# onboard_3.net
KiCad netlist of a schematic drawn in EAGLE
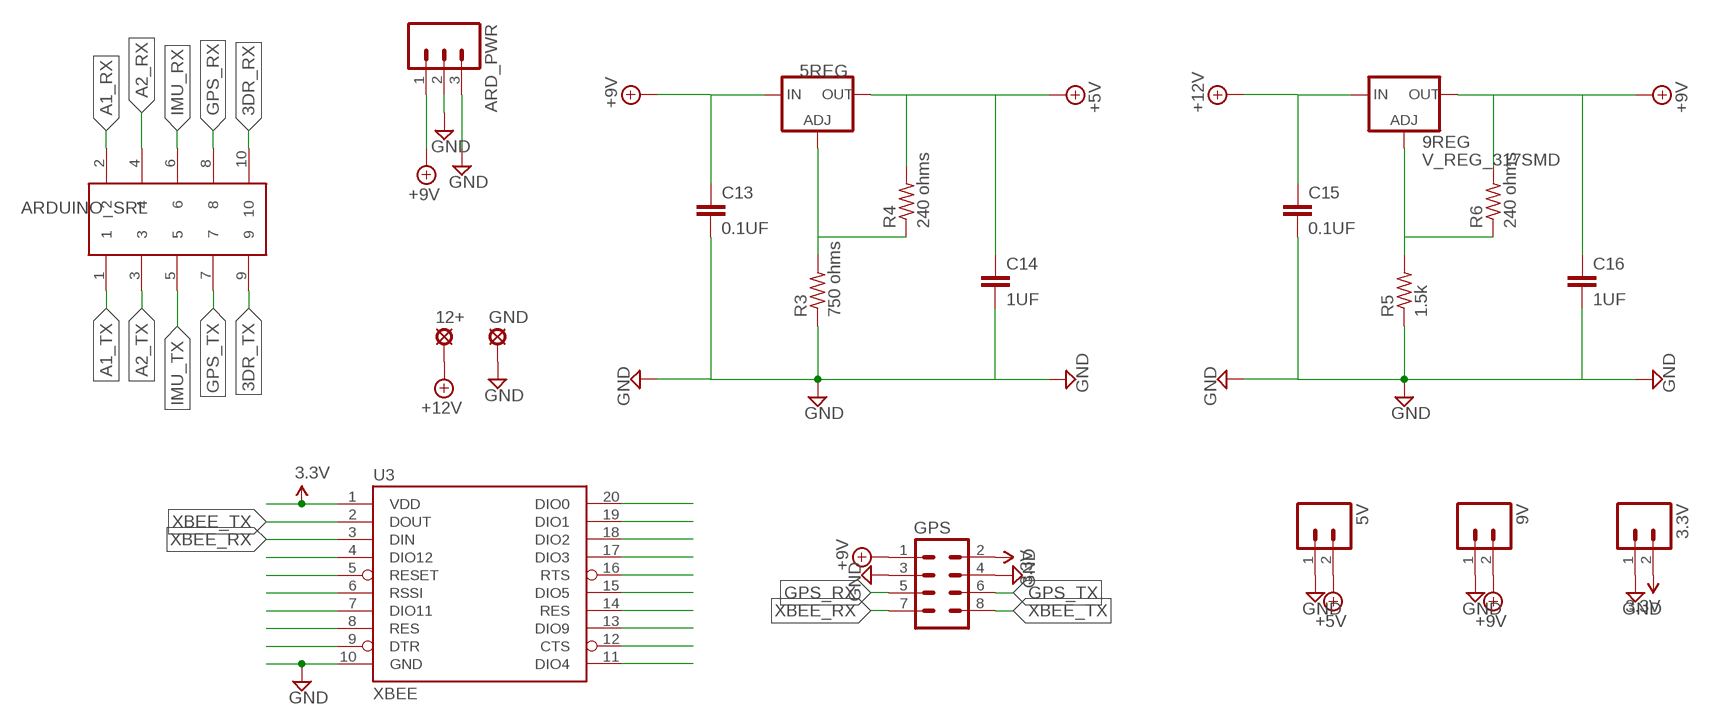
[diagram p0: schematic, sheet 1, part 1 of 2]
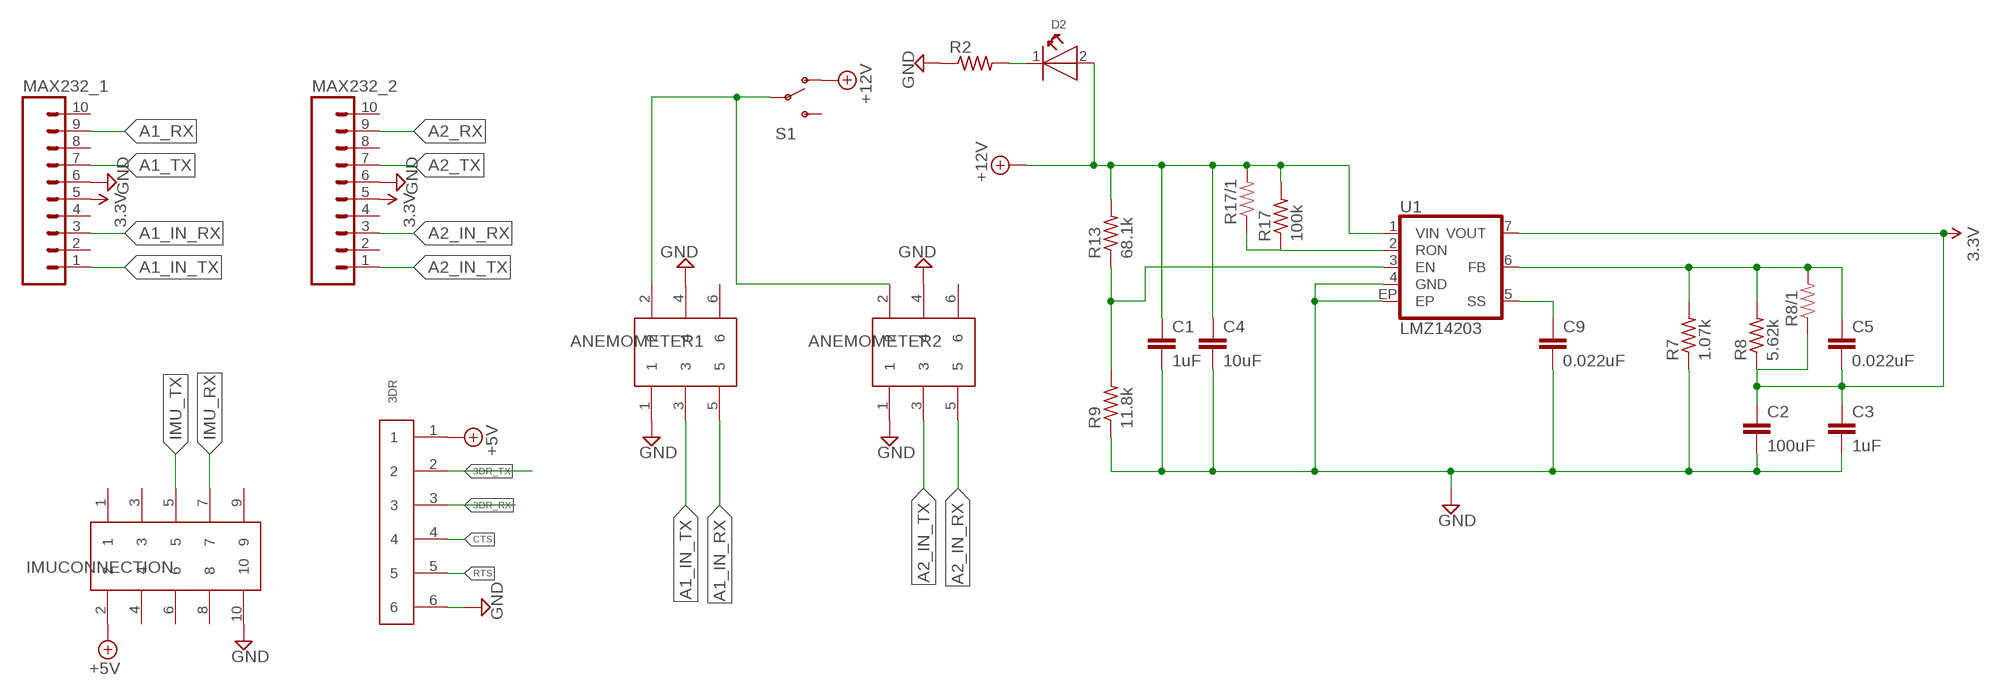
[diagram p1: schematic, sheet 1, part 2 of 2]

(export (version "E")
  (design (tool "Eeschema 10.0.6"))
  (components
    (comp (ref "3.3V")
      (value "M02")
      (footprint "eagle-import:02P")
      (libsource (lib "eagle-import") (part "M02"))
    )
    (comp (ref "3DR")
      (value "653006114822")
      (footprint "eagle-import:653006114822")
      (libsource (lib "eagle-import") (part "653006114822"))
    )
    (comp (ref "5REG")
      (value "V_REG_317SMD")
      (footprint "eagle-import:SOT223")
      (libsource (lib "eagle-import") (part "V_REG_317SMD"))
    )
    (comp (ref "5V")
      (value "M02")
      (footprint "eagle-import:02P")
      (libsource (lib "eagle-import") (part "M02"))
    )
    (comp (ref "9REG")
      (value "V_REG_317SMD")
      (footprint "eagle-import:SOT223")
      (libsource (lib "eagle-import") (part "V_REG_317SMD"))
    )
    (comp (ref "9V")
      (value "M02")
      (footprint "eagle-import:02P")
      (libsource (lib "eagle-import") (part "M02"))
    )
    (comp (ref "12+")
      (value "SE14")
      (footprint "eagle-import:SE14")
      (libsource (lib "eagle-import") (part "SE14"))
    )
    (comp (ref "ANEMOMETER1")
      (value "61200622323")
      (footprint "eagle-import:61200622323")
      (libsource (lib "eagle-import") (part "61200622323"))
    )
    (comp (ref "ANEMOMETER2")
      (value "61200622323")
      (footprint "eagle-import:61200622323")
      (libsource (lib "eagle-import") (part "61200622323"))
    )
    (comp (ref "ARDUINO_SRL")
      (value "61201022323")
      (footprint "eagle-import:61201022323")
      (libsource (lib "eagle-import") (part "61201022323"))
    )
    (comp (ref "ARD_PWR")
      (value "M03")
      (footprint "eagle-import:03P")
      (libsource (lib "eagle-import") (part "M03"))
    )
    (comp (ref "C1")
      (value "1uF")
      (footprint "eagle-import:0805")
      (fields (field (name "MF") "VISHAY/SPRAGUE") (field (name "MPN") "1C10Z5U104M050R"))
      (libsource (lib "eagle-import") (part "1UF-25V-10%(0805)"))
    )
    (comp (ref "C2")
      (value "100uF")
      (footprint "eagle-import:1206")
      (libsource (lib "eagle-import") (part "CAP1206"))
    )
    (comp (ref "C3")
      (value "1uF")
      (footprint "eagle-import:0805")
      (fields (field (name "MF") "VISHAY/SPRAGUE") (field (name "MPN") "1C10Z5U104M050R"))
      (libsource (lib "eagle-import") (part "1UF-25V-10%(0805)"))
    )
    (comp (ref "C4")
      (value "10uF")
      (footprint "eagle-import:0805")
      (libsource (lib "eagle-import") (part "CAP0805"))
    )
    (comp (ref "C5")
      (value "0.022uF")
      (footprint "eagle-import:0603-CAP")
      (libsource (lib "eagle-import") (part "CAP0603-CAP"))
    )
    (comp (ref "C9")
      (value "0.022uF")
      (footprint "eagle-import:0603-CAP")
      (libsource (lib "eagle-import") (part "CAP0603-CAP"))
    )
    (comp (ref "C13")
      (value "0.1UF")
      (footprint "eagle-import:0805")
      (libsource (lib "eagle-import") (part "1UF-25V-10%(0805)"))
    )
    (comp (ref "C14")
      (value "1UF")
      (footprint "eagle-import:0805")
      (libsource (lib "eagle-import") (part "1UF-25V-10%(0805)"))
    )
    (comp (ref "C15")
      (value "0.1UF")
      (footprint "eagle-import:0805")
      (libsource (lib "eagle-import") (part "1UF-25V-10%(0805)"))
    )
    (comp (ref "C16")
      (value "1UF")
      (footprint "eagle-import:0805")
      (libsource (lib "eagle-import") (part "1UF-25V-10%(0805)"))
    )
    (comp (ref "D2")
      (value "WL-SMCW-150120BS75000-B")
      (footprint "eagle-import:1206")
      (fields
        (field (name "MANUFACTURER") "Würth Elektronik eiSos GmbH")
        (field (name "CREATED-BY") "Christin Otto")
      )
      (libsource (lib "eagle-import") (part "WL-SMCW-150120BS75000-B"))
    )
    (comp (ref "GND")
      (value "SE14")
      (footprint "eagle-import:SE14")
      (libsource (lib "eagle-import") (part "SE14"))
    )
    (comp (ref "GPS")
      (value "M04X2")
      (footprint "eagle-import:2X4")
      (libsource (lib "eagle-import") (part "M04X2"))
    )
    (comp (ref "IMUCONNECTION")
      (value "62501021621")
      (footprint "eagle-import:62501021621")
      (libsource (lib "eagle-import") (part "62501021621"))
    )
    (comp (ref "MAX232_1")
      (value "M10")
      (footprint "eagle-import:10P")
      (libsource (lib "eagle-import") (part "M10"))
    )
    (comp (ref "MAX232_2")
      (value "M10")
      (footprint "eagle-import:10P")
      (libsource (lib "eagle-import") (part "M10"))
    )
    (comp (ref "R2")
      (value "R-US_M2012")
      (footprint "eagle-import:M2012")
      (libsource (lib "eagle-import") (part "resistor_R-US_M2012"))
    )
    (comp (ref "R3")
      (value "750 ohms")
      (footprint "eagle-import:M2012")
      (libsource (lib "eagle-import") (part "R-US_M2012"))
    )
    (comp (ref "R4")
      (value "240 ohms")
      (footprint "eagle-import:M2012")
      (libsource (lib "eagle-import") (part "R-US_M2012"))
    )
    (comp (ref "R5")
      (value "1.5k")
      (footprint "eagle-import:M2012")
      (libsource (lib "eagle-import") (part "R-US_M2012"))
    )
    (comp (ref "R6")
      (value "240 ohms")
      (footprint "eagle-import:M2012")
      (libsource (lib "eagle-import") (part "R-US_M2012"))
    )
    (comp (ref "R7")
      (value "1.07k")
      (footprint "eagle-import:M2012")
      (libsource (lib "eagle-import") (part "resistor_R-US_M2012"))
    )
    (comp (ref "R8")
      (value "5.62k")
      (footprint "eagle-import:M2012")
      (libsource (lib "eagle-import") (part "resistor_R-US_M2012"))
    )
    (comp (ref "R8/1")
      (value "RESISTORPTH-1/2W")
      (footprint "eagle-import:AXIAL-0.5")
      (libsource (lib "eagle-import") (part "RESISTORPTH-1/2W"))
    )
    (comp (ref "R9")
      (value "11.8k")
      (footprint "eagle-import:M2012")
      (libsource (lib "eagle-import") (part "resistor_R-US_M2012"))
    )
    (comp (ref "R13")
      (value "68.1k")
      (footprint "eagle-import:M2012")
      (libsource (lib "eagle-import") (part "resistor_R-US_M2012"))
    )
    (comp (ref "R17")
      (value "100k")
      (footprint "eagle-import:M2012")
      (libsource (lib "eagle-import") (part "resistor_R-US_M2012"))
    )
    (comp (ref "R17/1")
      (value "RESISTORPTH-1/2W")
      (footprint "eagle-import:AXIAL-0.5")
      (libsource (lib "eagle-import") (part "RESISTORPTH-1/2W"))
    )
    (comp (ref "S1")
      (value "SWITCH-SPDTSMD2")
      (footprint "eagle-import:SWITCH-SPDT-SMD")
      (libsource (lib "eagle-import") (part "SWITCH-SPDTSMD2"))
    )
    (comp (ref "U1")
      (value "LMZ14203")
      (footprint "eagle-import:TO-PMOD-7")
      (libsource (lib "eagle-import") (part "LMZ14203"))
    )
    (comp (ref "U3")
      (value "XBEE")
      (footprint "eagle-import:XBEE-1")
      (libsource (lib "eagle-import") (part "XBEE-1B1"))
    )
  )
  (nets
    (net (code "1") (name "+5V") (class "Default")
      (node (ref "3DR") (pin "1") (pinfunction "1_1") (pintype "passive"))
      (node (ref "5REG") (pin "2") (pinfunction "OUT_2") (pintype "output"))
      (node (ref "5V") (pin "2") (pinfunction "2_2") (pintype "passive"))
      (node (ref "C14") (pin "1") (pinfunction "1_1") (pintype "passive"))
      (node (ref "IMUCONNECTION") (pin "2") (pinfunction "2_2") (pintype "passive"))
      (node (ref "R4") (pin "2") (pinfunction "2_2") (pintype "passive"))
    )
    (net (code "2") (name "+9V") (class "Default")
      (node (ref "5REG") (pin "3") (pinfunction "IN_3") (pintype "input"))
      (node (ref "9REG") (pin "2") (pinfunction "OUT_2") (pintype "output"))
      (node (ref "9V") (pin "2") (pinfunction "2_2") (pintype "passive"))
      (node (ref "ARD_PWR") (pin "1") (pinfunction "1_1") (pintype "passive"))
      (node (ref "C13") (pin "1") (pinfunction "1_1") (pintype "passive"))
      (node (ref "C16") (pin "1") (pinfunction "1_1") (pintype "passive"))
      (node (ref "GPS") (pin "1") (pinfunction "1_1") (pintype "passive"))
      (node (ref "R6") (pin "2") (pinfunction "2_2") (pintype "passive"))
    )
    (net (code "3") (name "+12V") (class "Default")
      (node (ref "12+") (pin "MP") (pinfunction "MP_MP") (pintype "passive"))
      (node (ref "9REG") (pin "3") (pinfunction "IN_3") (pintype "input"))
      (node (ref "C1") (pin "1") (pinfunction "1_1") (pintype "passive"))
      (node (ref "C15") (pin "1") (pinfunction "1_1") (pintype "passive"))
      (node (ref "C4") (pin "1") (pinfunction "1_1") (pintype "passive"))
      (node (ref "D2") (pin "2") (pinfunction "A_2") (pintype "bidirectional"))
      (node (ref "R13") (pin "2") (pinfunction "2_2") (pintype "passive"))
      (node (ref "R17") (pin "2") (pinfunction "2_2") (pintype "passive"))
      (node (ref "R17/1") (pin "P$2") (pinfunction "2_P$2") (pintype "passive"))
      (node (ref "S1") (pin "1") (pinfunction "O_1") (pintype "passive"))
      (node (ref "U1") (pin "1") (pinfunction "VIN_1") (pintype "bidirectional"))
    )
    (net (code "4") (name "3.3V") (class "Default")
      (node (ref "3.3V") (pin "2") (pinfunction "2_2") (pintype "passive"))
      (node (ref "C2") (pin "1") (pinfunction "1_1") (pintype "passive"))
      (node (ref "C3") (pin "1") (pinfunction "1_1") (pintype "passive"))
      (node (ref "C5") (pin "2") (pinfunction "2_2") (pintype "passive"))
      (node (ref "GPS") (pin "2") (pinfunction "2_2") (pintype "passive"))
      (node (ref "MAX232_1") (pin "5") (pinfunction "5_5") (pintype "passive"))
      (node (ref "MAX232_2") (pin "5") (pinfunction "5_5") (pintype "passive"))
      (node (ref "R8") (pin "1") (pinfunction "1_1") (pintype "passive"))
      (node (ref "R8/1") (pin "P$1") (pinfunction "1_P$1") (pintype "passive"))
      (node (ref "U1") (pin "7") (pinfunction "VOUT_7") (pintype "bidirectional"))
      (node (ref "U3") (pin "1") (pinfunction "VDD_1") (pintype "power_in"))
    )
    (net (code "5") (name "3DR_RX") (class "Default")
      (node (ref "3DR") (pin "3") (pinfunction "3_3") (pintype "passive"))
      (node (ref "ARDUINO_SRL") (pin "10") (pinfunction "10_10") (pintype "passive"))
    )
    (net (code "6") (name "3DR_TX") (class "Default")
      (node (ref "3DR") (pin "2") (pinfunction "2_2") (pintype "passive"))
      (node (ref "ARDUINO_SRL") (pin "9") (pinfunction "9_9") (pintype "passive"))
    )
    (net (code "7") (name "A1_IN_RX") (class "Default")
      (node (ref "ANEMOMETER1") (pin "5") (pinfunction "5_5") (pintype "passive"))
      (node (ref "MAX232_1") (pin "3") (pinfunction "3_3") (pintype "passive"))
    )
    (net (code "8") (name "A1_IN_TX") (class "Default")
      (node (ref "ANEMOMETER1") (pin "3") (pinfunction "3_3") (pintype "passive"))
      (node (ref "MAX232_1") (pin "1") (pinfunction "1_1") (pintype "passive"))
    )
    (net (code "9") (name "A1_RX") (class "Default")
      (node (ref "ARDUINO_SRL") (pin "2") (pinfunction "2_2") (pintype "passive"))
      (node (ref "MAX232_1") (pin "9") (pinfunction "9_9") (pintype "passive"))
    )
    (net (code "10") (name "A1_TX") (class "Default")
      (node (ref "ARDUINO_SRL") (pin "1") (pinfunction "1_1") (pintype "passive"))
      (node (ref "MAX232_1") (pin "7") (pinfunction "7_7") (pintype "passive"))
    )
    (net (code "11") (name "A2_IN_RX") (class "Default")
      (node (ref "ANEMOMETER2") (pin "5") (pinfunction "5_5") (pintype "passive"))
      (node (ref "MAX232_2") (pin "3") (pinfunction "3_3") (pintype "passive"))
    )
    (net (code "12") (name "A2_IN_TX") (class "Default")
      (node (ref "ANEMOMETER2") (pin "3") (pinfunction "3_3") (pintype "passive"))
      (node (ref "MAX232_2") (pin "1") (pinfunction "1_1") (pintype "passive"))
    )
    (net (code "13") (name "A2_RX") (class "Default")
      (node (ref "ARDUINO_SRL") (pin "4") (pinfunction "4_4") (pintype "passive"))
      (node (ref "MAX232_2") (pin "9") (pinfunction "9_9") (pintype "passive"))
    )
    (net (code "14") (name "A2_TX") (class "Default")
      (node (ref "ARDUINO_SRL") (pin "3") (pinfunction "3_3") (pintype "passive"))
      (node (ref "MAX232_2") (pin "7") (pinfunction "7_7") (pintype "passive"))
    )
    (net (code "15") (name "CTS") (class "Default")
      (node (ref "3DR") (pin "4") (pinfunction "4_4") (pintype "passive"))
    )
    (net (code "16") (name "GND") (class "Default")
      (node (ref "3.3V") (pin "1") (pinfunction "1_1") (pintype "passive"))
      (node (ref "3DR") (pin "6") (pinfunction "6_6") (pintype "passive"))
      (node (ref "5V") (pin "1") (pinfunction "1_1") (pintype "passive"))
      (node (ref "9V") (pin "1") (pinfunction "1_1") (pintype "passive"))
      (node (ref "ANEMOMETER1") (pin "1") (pinfunction "1_1") (pintype "passive"))
      (node (ref "ANEMOMETER1") (pin "4") (pinfunction "4_4") (pintype "passive"))
      (node (ref "ANEMOMETER2") (pin "1") (pinfunction "1_1") (pintype "passive"))
      (node (ref "ANEMOMETER2") (pin "4") (pinfunction "4_4") (pintype "passive"))
      (node (ref "ARD_PWR") (pin "2") (pinfunction "2_2") (pintype "passive"))
      (node (ref "ARD_PWR") (pin "3") (pinfunction "3_3") (pintype "passive"))
      (node (ref "C1") (pin "2") (pinfunction "2_2") (pintype "passive"))
      (node (ref "C13") (pin "2") (pinfunction "2_2") (pintype "passive"))
      (node (ref "C14") (pin "2") (pinfunction "2_2") (pintype "passive"))
      (node (ref "C15") (pin "2") (pinfunction "2_2") (pintype "passive"))
      (node (ref "C16") (pin "2") (pinfunction "2_2") (pintype "passive"))
      (node (ref "C2") (pin "2") (pinfunction "2_2") (pintype "passive"))
      (node (ref "C3") (pin "2") (pinfunction "2_2") (pintype "passive"))
      (node (ref "C4") (pin "2") (pinfunction "2_2") (pintype "passive"))
      (node (ref "C9") (pin "2") (pinfunction "2_2") (pintype "passive"))
      (node (ref "GND") (pin "MP") (pinfunction "MP_MP") (pintype "passive"))
      (node (ref "GPS") (pin "3") (pinfunction "3_3") (pintype "passive"))
      (node (ref "GPS") (pin "4") (pinfunction "4_4") (pintype "passive"))
      (node (ref "IMUCONNECTION") (pin "10") (pinfunction "10_10") (pintype "passive"))
      (node (ref "MAX232_1") (pin "6") (pinfunction "6_6") (pintype "passive"))
      (node (ref "MAX232_2") (pin "6") (pinfunction "6_6") (pintype "passive"))
      (node (ref "R2") (pin "1") (pinfunction "1_1") (pintype "passive"))
      (node (ref "R3") (pin "1") (pinfunction "1_1") (pintype "passive"))
      (node (ref "R5") (pin "1") (pinfunction "1_1") (pintype "passive"))
      (node (ref "R7") (pin "1") (pinfunction "1_1") (pintype "passive"))
      (node (ref "R9") (pin "1") (pinfunction "1_1") (pintype "passive"))
      (node (ref "U1") (pin "4") (pinfunction "GND_4") (pintype "bidirectional"))
      (node (ref "U1") (pin "EP") (pinfunction "EP_EP") (pintype "bidirectional"))
      (node (ref "U3") (pin "10") (pinfunction "GND_10") (pintype "power_in"))
    )
    (net (code "17") (name "GPS_RX") (class "Default")
      (node (ref "ARDUINO_SRL") (pin "8") (pinfunction "8_8") (pintype "passive"))
      (node (ref "GPS") (pin "5") (pinfunction "5_5") (pintype "passive"))
    )
    (net (code "18") (name "GPS_TX") (class "Default")
      (node (ref "ARDUINO_SRL") (pin "7") (pinfunction "7_7") (pintype "passive"))
      (node (ref "GPS") (pin "6") (pinfunction "6_6") (pintype "passive"))
    )
    (net (code "19") (name "IMU_RX") (class "Default")
      (node (ref "ARDUINO_SRL") (pin "6") (pinfunction "6_6") (pintype "passive"))
      (node (ref "IMUCONNECTION") (pin "7") (pinfunction "7_7") (pintype "passive"))
    )
    (net (code "20") (name "IMU_TX") (class "Default")
      (node (ref "ARDUINO_SRL") (pin "5") (pinfunction "5_5") (pintype "passive"))
      (node (ref "IMUCONNECTION") (pin "5") (pinfunction "5_5") (pintype "passive"))
    )
    (net (code "21") (name "Net-(5REG-ADJ)") (class "Default")
      (node (ref "5REG") (pin "1") (pinfunction "ADJ_1") (pintype "input"))
      (node (ref "R3") (pin "2") (pinfunction "2_2") (pintype "passive"))
      (node (ref "R4") (pin "1") (pinfunction "1_1") (pintype "passive"))
    )
    (net (code "22") (name "Net-(9REG-ADJ)") (class "Default")
      (node (ref "9REG") (pin "1") (pinfunction "ADJ_1") (pintype "input"))
      (node (ref "R5") (pin "2") (pinfunction "2_2") (pintype "passive"))
      (node (ref "R6") (pin "1") (pinfunction "1_1") (pintype "passive"))
    )
    (net (code "23") (name "Net-(D2-K)") (class "Default")
      (node (ref "D2") (pin "1") (pinfunction "K_1") (pintype "bidirectional"))
      (node (ref "R2") (pin "2") (pinfunction "2_2") (pintype "passive"))
    )
    (net (code "24") (name "Net-(R8/1-2)") (class "Default")
      (node (ref "C5") (pin "1") (pinfunction "1_1") (pintype "passive"))
      (node (ref "R7") (pin "2") (pinfunction "2_2") (pintype "passive"))
      (node (ref "R8") (pin "2") (pinfunction "2_2") (pintype "passive"))
      (node (ref "R8/1") (pin "P$2") (pinfunction "2_P$2") (pintype "passive"))
      (node (ref "U1") (pin "6") (pinfunction "FB_6") (pintype "bidirectional"))
    )
    (net (code "25") (name "Net-(R17/1-1)") (class "Default")
      (node (ref "R17") (pin "1") (pinfunction "1_1") (pintype "passive"))
      (node (ref "R17/1") (pin "P$1") (pinfunction "1_P$1") (pintype "passive"))
      (node (ref "U1") (pin "2") (pinfunction "RON_2") (pintype "bidirectional"))
    )
    (net (code "26") (name "Net-(S1-P)") (class "Default")
      (node (ref "ANEMOMETER1") (pin "2") (pinfunction "2_2") (pintype "passive"))
      (node (ref "ANEMOMETER2") (pin "2") (pinfunction "2_2") (pintype "passive"))
      (node (ref "S1") (pin "2") (pinfunction "P_2") (pintype "passive"))
    )
    (net (code "27") (name "Net-(U1-EN)") (class "Default")
      (node (ref "R13") (pin "1") (pinfunction "1_1") (pintype "passive"))
      (node (ref "R9") (pin "2") (pinfunction "2_2") (pintype "passive"))
      (node (ref "U1") (pin "3") (pinfunction "EN_3") (pintype "bidirectional"))
    )
    (net (code "28") (name "Net-(U1-SS)") (class "Default")
      (node (ref "C9") (pin "1") (pinfunction "1_1") (pintype "passive"))
      (node (ref "U1") (pin "5") (pinfunction "SS_5") (pintype "bidirectional"))
    )
    (net (code "29") (name "RTS") (class "Default")
      (node (ref "3DR") (pin "5") (pinfunction "5_5") (pintype "passive"))
    )
    (net (code "30") (name "XBEE_RX") (class "Default")
      (node (ref "GPS") (pin "7") (pinfunction "7_7") (pintype "passive"))
      (node (ref "U3") (pin "3") (pinfunction "DIN_3") (pintype "input"))
    )
    (net (code "31") (name "XBEE_TX") (class "Default")
      (node (ref "GPS") (pin "8") (pinfunction "8_8") (pintype "passive"))
      (node (ref "U3") (pin "2") (pinfunction "DOUT_2") (pintype "output"))
    )
    (net (code "32") (name "unconnected-(ANEMOMETER1-Pad6)") (class "Default")
      (node (ref "ANEMOMETER1") (pin "6") (pinfunction "6_6") (pintype "passive"))
    )
    (net (code "33") (name "unconnected-(ANEMOMETER2-Pad6)") (class "Default")
      (node (ref "ANEMOMETER2") (pin "6") (pinfunction "6_6") (pintype "passive"))
    )
    (net (code "34") (name "unconnected-(IMUCONNECTION-Pad1)") (class "Default")
      (node (ref "IMUCONNECTION") (pin "1") (pinfunction "1_1") (pintype "passive"))
    )
    (net (code "35") (name "unconnected-(IMUCONNECTION-Pad3)") (class "Default")
      (node (ref "IMUCONNECTION") (pin "3") (pinfunction "3_3") (pintype "passive"))
    )
    (net (code "36") (name "unconnected-(IMUCONNECTION-Pad4)") (class "Default")
      (node (ref "IMUCONNECTION") (pin "4") (pinfunction "4_4") (pintype "passive"))
    )
    (net (code "37") (name "unconnected-(IMUCONNECTION-Pad6)") (class "Default")
      (node (ref "IMUCONNECTION") (pin "6") (pinfunction "6_6") (pintype "passive"))
    )
    (net (code "38") (name "unconnected-(IMUCONNECTION-Pad8)") (class "Default")
      (node (ref "IMUCONNECTION") (pin "8") (pinfunction "8_8") (pintype "passive"))
    )
    (net (code "39") (name "unconnected-(IMUCONNECTION-Pad9)") (class "Default")
      (node (ref "IMUCONNECTION") (pin "9") (pinfunction "9_9") (pintype "passive"))
    )
    (net (code "40") (name "unconnected-(MAX232_1-Pad2)") (class "Default")
      (node (ref "MAX232_1") (pin "2") (pinfunction "2_2") (pintype "passive"))
    )
    (net (code "41") (name "unconnected-(MAX232_1-Pad4)") (class "Default")
      (node (ref "MAX232_1") (pin "4") (pinfunction "4_4") (pintype "passive"))
    )
    (net (code "42") (name "unconnected-(MAX232_1-Pad8)") (class "Default")
      (node (ref "MAX232_1") (pin "8") (pinfunction "8_8") (pintype "passive"))
    )
    (net (code "43") (name "unconnected-(MAX232_1-Pad10)") (class "Default")
      (node (ref "MAX232_1") (pin "10") (pinfunction "10_10") (pintype "passive"))
    )
    (net (code "44") (name "unconnected-(MAX232_2-Pad2)") (class "Default")
      (node (ref "MAX232_2") (pin "2") (pinfunction "2_2") (pintype "passive"))
    )
    (net (code "45") (name "unconnected-(MAX232_2-Pad4)") (class "Default")
      (node (ref "MAX232_2") (pin "4") (pinfunction "4_4") (pintype "passive"))
    )
    (net (code "46") (name "unconnected-(MAX232_2-Pad8)") (class "Default")
      (node (ref "MAX232_2") (pin "8") (pinfunction "8_8") (pintype "passive"))
    )
    (net (code "47") (name "unconnected-(MAX232_2-Pad10)") (class "Default")
      (node (ref "MAX232_2") (pin "10") (pinfunction "10_10") (pintype "passive"))
    )
    (net (code "48") (name "unconnected-(S1-S-Pad3)") (class "Default")
      (node (ref "S1") (pin "3") (pinfunction "S_3") (pintype "passive"))
    )
    (net (code "49") (name "unconnected-(U3-CTS-Pad12)") (class "Default")
      (node (ref "U3") (pin "12") (pinfunction "CTS_12") (pintype "output"))
    )
    (net (code "50") (name "unconnected-(U3-DIO0-Pad20)") (class "Default")
      (node (ref "U3") (pin "20") (pinfunction "DIO0_20") (pintype "bidirectional"))
    )
    (net (code "51") (name "unconnected-(U3-DIO1-Pad19)") (class "Default")
      (node (ref "U3") (pin "19") (pinfunction "DIO1_19") (pintype "bidirectional"))
    )
    (net (code "52") (name "unconnected-(U3-DIO2-Pad18)") (class "Default")
      (node (ref "U3") (pin "18") (pinfunction "DIO2_18") (pintype "bidirectional"))
    )
    (net (code "53") (name "unconnected-(U3-DIO3-Pad17)") (class "Default")
      (node (ref "U3") (pin "17") (pinfunction "DIO3_17") (pintype "bidirectional"))
    )
    (net (code "54") (name "unconnected-(U3-DIO4-Pad11)") (class "Default")
      (node (ref "U3") (pin "11") (pinfunction "DIO4_11") (pintype "bidirectional"))
    )
    (net (code "55") (name "unconnected-(U3-DIO5-Pad15)") (class "Default")
      (node (ref "U3") (pin "15") (pinfunction "DIO5_15") (pintype "bidirectional"))
    )
    (net (code "56") (name "unconnected-(U3-DIO9-Pad13)") (class "Default")
      (node (ref "U3") (pin "13") (pinfunction "DIO9_13") (pintype "bidirectional"))
    )
    (net (code "57") (name "unconnected-(U3-DIO11-Pad7)") (class "Default")
      (node (ref "U3") (pin "7") (pinfunction "DIO11_7") (pintype "bidirectional"))
    )
    (net (code "58") (name "unconnected-(U3-DIO12-Pad4)") (class "Default")
      (node (ref "U3") (pin "4") (pinfunction "DIO12_4") (pintype "bidirectional"))
    )
    (net (code "59") (name "unconnected-(U3-DTR-Pad9)") (class "Default")
      (node (ref "U3") (pin "9") (pinfunction "DTR_9") (pintype "bidirectional"))
    )
    (net (code "60") (name "unconnected-(U3-RES-Pad8)") (class "Default")
      (node (ref "U3") (pin "8") (pinfunction "RES_8") (pintype "bidirectional"))
    )
    (net (code "61") (name "unconnected-(U3-RES-Pad14)") (class "Default")
      (node (ref "U3") (pin "14") (pinfunction "RES_14") (pintype "bidirectional"))
    )
    (net (code "62") (name "unconnected-(U3-RESET-Pad5)") (class "Default")
      (node (ref "U3") (pin "5") (pinfunction "RESET_5") (pintype "input"))
    )
    (net (code "63") (name "unconnected-(U3-RSSI-Pad6)") (class "Default")
      (node (ref "U3") (pin "6") (pinfunction "RSSI_6") (pintype "bidirectional"))
    )
    (net (code "64") (name "unconnected-(U3-RTS-Pad16)") (class "Default")
      (node (ref "U3") (pin "16") (pinfunction "RTS_16") (pintype "input"))
    )
  )
)
